# STM32_AUX.net
KiCad netlist of a schematic drawn in Altium Designer
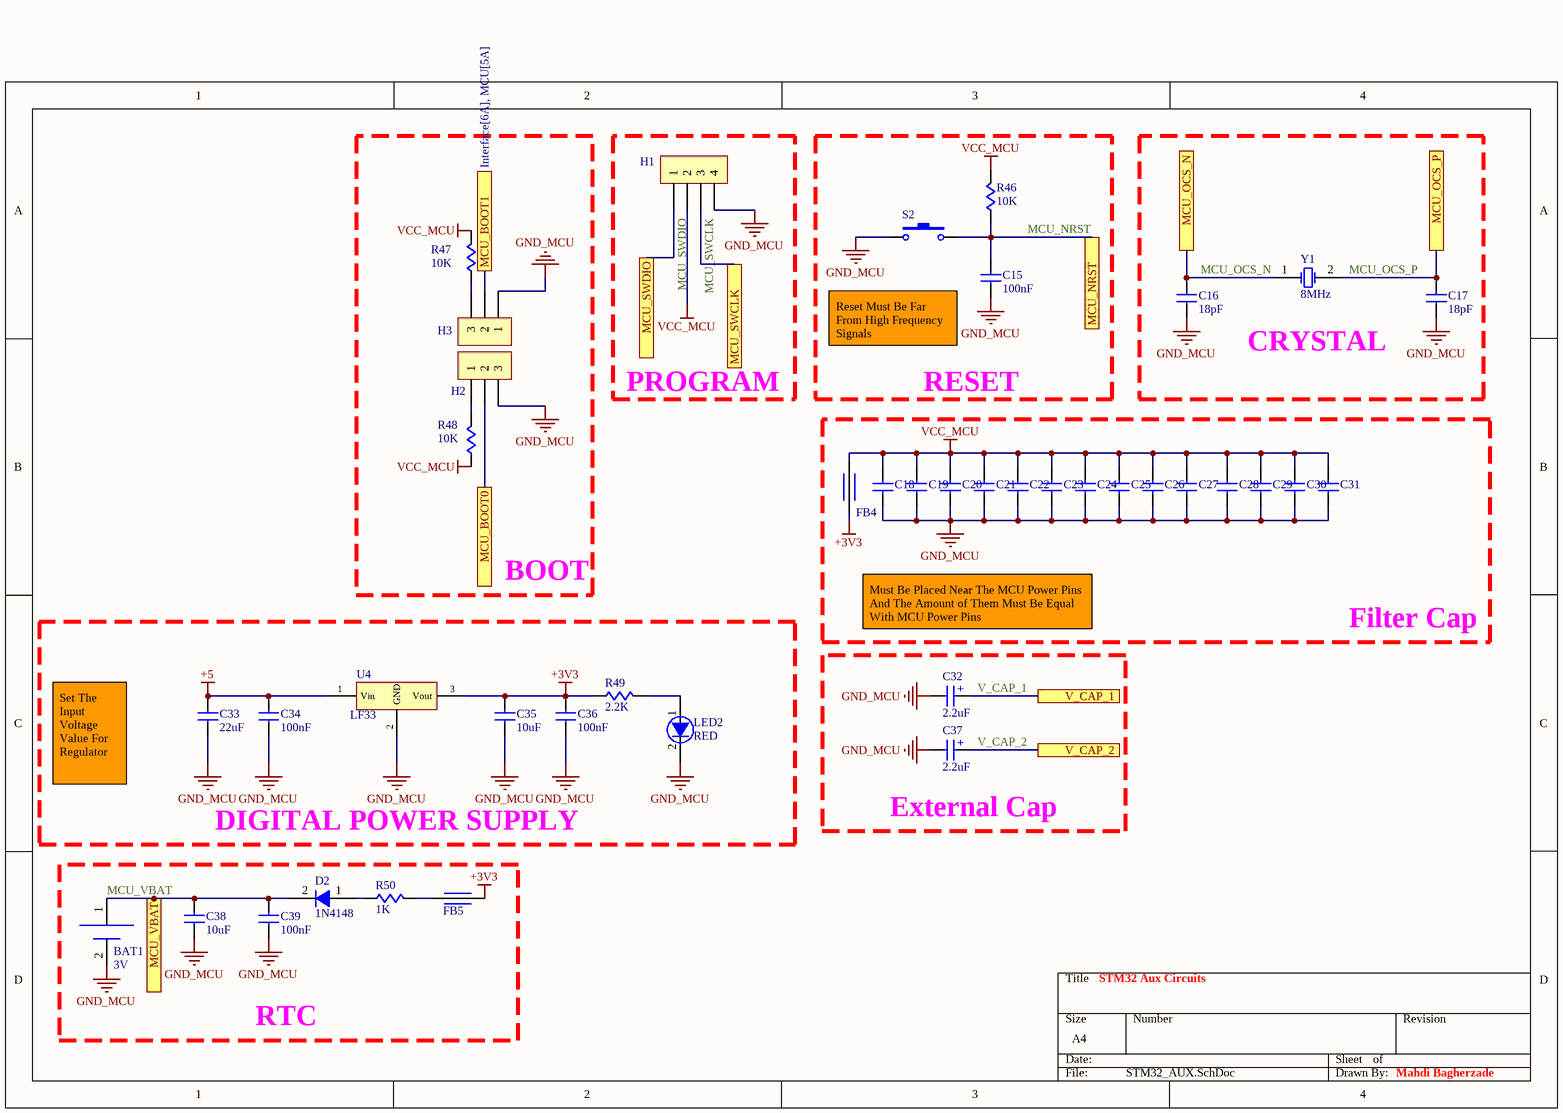
[diagram p0: STM32_AUX.SchDoc]

(export (version "E")
  (design (tool "Eeschema 10.0.6"))
  (components
    (comp (ref "BAT1")
      (value "Bat Holder 2016-SMD")
      (footprint "BAT-HOLDER-SMD-1220")
      (description "BATTERY")
      (fields (field (name "VOLTAGE") "3V") (field (name "PUBLISHER") "Mahdi Bagherzadeh"))
      (libsource (lib "Mahdi-Bagherzadeh") (part "BATTERY HOLDER"))
    )
    (comp (ref "C15")
      (value "100nF")
      (footprint "C-0805")
      (description "CAPACITOR")
      (fields
        (field (name "VOLTAGE") "50V")
        (field (name "TOLERANCE") "X7R")
        (field (name "PUBLISHER") "Mahdi Bagherzadeh")
      )
      (libsource (lib "Mahdi-Bagherzadeh") (part "CAP-CER"))
    )
    (comp (ref "C16")
      (value "18pF")
      (footprint "C-0805")
      (description "CAPACITOR")
      (fields
        (field (name "VOLTAGE") "50V")
        (field (name "TOLERANCE") "X7R")
        (field (name "PUBLISHER") "Mahdi Bagherzadeh")
      )
      (libsource (lib "Mahdi-Bagherzadeh") (part "CAP-CER"))
    )
    (comp (ref "C17")
      (value "18pF")
      (footprint "C-0805")
      (description "CAPACITOR")
      (fields
        (field (name "VOLTAGE") "50V")
        (field (name "TOLERANCE") "X7R")
        (field (name "PUBLISHER") "Mahdi Bagherzadeh")
      )
      (libsource (lib "Mahdi-Bagherzadeh") (part "CAP-CER"))
    )
    (comp (ref "C18")
      (value "CAP Cer 100nF-50V-X7R-SMD")
      (footprint "C-0805")
      (description "CAPACITOR")
      (fields
        (field (name "VOLTAGE") "50V")
        (field (name "TOLERANCE") "X7R")
        (field (name "PUBLISHER") "Mahdi Bagherzadeh")
      )
      (libsource (lib "Mahdi-Bagherzadeh") (part "CAP-CER"))
    )
    (comp (ref "C19")
      (value "CAP Cer 100nF-50V-X7R-SMD")
      (footprint "C-0805")
      (description "CAPACITOR")
      (fields
        (field (name "VOLTAGE") "50V")
        (field (name "TOLERANCE") "X7R")
        (field (name "PUBLISHER") "Mahdi Bagherzadeh")
      )
      (libsource (lib "Mahdi-Bagherzadeh") (part "CAP-CER"))
    )
    (comp (ref "C20")
      (value "CAP Cer 100nF-50V-X7R-SMD")
      (footprint "C-0805")
      (description "CAPACITOR")
      (fields
        (field (name "VOLTAGE") "50V")
        (field (name "TOLERANCE") "X7R")
        (field (name "PUBLISHER") "Mahdi Bagherzadeh")
      )
      (libsource (lib "Mahdi-Bagherzadeh") (part "CAP-CER"))
    )
    (comp (ref "C21")
      (value "CAP Cer 100nF-50V-X7R-SMD")
      (footprint "C-0805")
      (description "CAPACITOR")
      (fields
        (field (name "VOLTAGE") "50V")
        (field (name "TOLERANCE") "X7R")
        (field (name "PUBLISHER") "Mahdi Bagherzadeh")
      )
      (libsource (lib "Mahdi-Bagherzadeh") (part "CAP-CER"))
    )
    (comp (ref "C22")
      (value "CAP Cer 100nF-50V-X7R-SMD")
      (footprint "C-0805")
      (description "CAPACITOR")
      (fields
        (field (name "VOLTAGE") "50V")
        (field (name "TOLERANCE") "X7R")
        (field (name "PUBLISHER") "Mahdi Bagherzadeh")
      )
      (libsource (lib "Mahdi-Bagherzadeh") (part "CAP-CER"))
    )
    (comp (ref "C23")
      (value "CAP Cer 100nF-50V-X7R-SMD")
      (footprint "C-0805")
      (description "CAPACITOR")
      (fields
        (field (name "VOLTAGE") "50V")
        (field (name "TOLERANCE") "X7R")
        (field (name "PUBLISHER") "Mahdi Bagherzadeh")
      )
      (libsource (lib "Mahdi-Bagherzadeh") (part "CAP-CER"))
    )
    (comp (ref "C24")
      (value "CAP Cer 100nF-50V-X7R-SMD")
      (footprint "C-0805")
      (description "CAPACITOR")
      (fields
        (field (name "VOLTAGE") "50V")
        (field (name "TOLERANCE") "X7R")
        (field (name "PUBLISHER") "Mahdi Bagherzadeh")
      )
      (libsource (lib "Mahdi-Bagherzadeh") (part "CAP-CER"))
    )
    (comp (ref "C25")
      (value "CAP Cer 100nF-50V-X7R-SMD")
      (footprint "C-0805")
      (description "CAPACITOR")
      (fields
        (field (name "VOLTAGE") "50V")
        (field (name "TOLERANCE") "X7R")
        (field (name "PUBLISHER") "Mahdi Bagherzadeh")
      )
      (libsource (lib "Mahdi-Bagherzadeh") (part "CAP-CER"))
    )
    (comp (ref "C26")
      (value "CAP Cer 100nF-50V-X7R-SMD")
      (footprint "C-0805")
      (description "CAPACITOR")
      (fields
        (field (name "VOLTAGE") "50V")
        (field (name "TOLERANCE") "X7R")
        (field (name "PUBLISHER") "Mahdi Bagherzadeh")
      )
      (libsource (lib "Mahdi-Bagherzadeh") (part "CAP-CER"))
    )
    (comp (ref "C27")
      (value "CAP Cer 100nF-50V-X7R-SMD")
      (footprint "C-0805")
      (description "CAPACITOR")
      (fields
        (field (name "VOLTAGE") "50V")
        (field (name "TOLERANCE") "X7R")
        (field (name "PUBLISHER") "Mahdi Bagherzadeh")
      )
      (libsource (lib "Mahdi-Bagherzadeh") (part "CAP-CER"))
    )
    (comp (ref "C28")
      (value "CAP Cer 100nF-50V-X7R-SMD")
      (footprint "C-0805")
      (description "CAPACITOR")
      (fields
        (field (name "VOLTAGE") "50V")
        (field (name "TOLERANCE") "X7R")
        (field (name "PUBLISHER") "Mahdi Bagherzadeh")
      )
      (libsource (lib "Mahdi-Bagherzadeh") (part "CAP-CER"))
    )
    (comp (ref "C29")
      (value "CAP Cer 100nF-50V-X7R-SMD")
      (footprint "C-0805")
      (description "CAPACITOR")
      (fields
        (field (name "VOLTAGE") "50V")
        (field (name "TOLERANCE") "X7R")
        (field (name "PUBLISHER") "Mahdi Bagherzadeh")
      )
      (libsource (lib "Mahdi-Bagherzadeh") (part "CAP-CER"))
    )
    (comp (ref "C30")
      (value "CAP Cer 100nF-50V-X7R-SMD")
      (footprint "C-0805")
      (description "CAPACITOR")
      (fields
        (field (name "VOLTAGE") "50V")
        (field (name "TOLERANCE") "X7R")
        (field (name "PUBLISHER") "Mahdi Bagherzadeh")
      )
      (libsource (lib "Mahdi-Bagherzadeh") (part "CAP-CER"))
    )
    (comp (ref "C31")
      (value "CAP Cer 100nF-50V-X7R-SMD")
      (footprint "C-0805")
      (description "CAPACITOR")
      (fields
        (field (name "VOLTAGE") "50V")
        (field (name "TOLERANCE") "X7R")
        (field (name "PUBLISHER") "Mahdi Bagherzadeh")
      )
      (libsource (lib "Mahdi-Bagherzadeh") (part "CAP-CER"))
    )
    (comp (ref "C32")
      (value "2.2uF")
      (footprint "TAN-A")
      (description "CAPACITOR")
      (fields
        (field (name "VOLTAGE") "10V")
        (field (name "Comment") "CAP Tantal 2.2uF-10V-A-SMD")
        (field (name "PUBLISHER") "Mahdi Bagherzadeh")
      )
      (libsource (lib "Mahdi-Bagherzadeh") (part "CAP-TAN"))
    )
    (comp (ref "C33")
      (value "22uF")
      (footprint "C-0805")
      (description "CAPACITOR")
      (fields
        (field (name "VOLTAGE") "50V")
        (field (name "TOLERANCE") "X7R")
        (field (name "PUBLISHER") "Mahdi Bagherzadeh")
      )
      (libsource (lib "Mahdi-Bagherzadeh") (part "CAP-CER"))
    )
    (comp (ref "C34")
      (value "100nF")
      (footprint "C-0805")
      (description "CAPACITOR")
      (fields
        (field (name "VOLTAGE") "50V")
        (field (name "TOLERANCE") "X7R")
        (field (name "PUBLISHER") "Mahdi Bagherzadeh")
      )
      (libsource (lib "Mahdi-Bagherzadeh") (part "CAP-CER"))
    )
    (comp (ref "C35")
      (value "10uF")
      (footprint "C-0805")
      (description "CAPACITOR")
      (fields
        (field (name "VOLTAGE") "50V")
        (field (name "TOLERANCE") "X7R")
        (field (name "PUBLISHER") "Mahdi Bagherzadeh")
      )
      (libsource (lib "Mahdi-Bagherzadeh") (part "CAP-CER"))
    )
    (comp (ref "C36")
      (value "100nF")
      (footprint "C-0805")
      (description "CAPACITOR")
      (fields
        (field (name "VOLTAGE") "50V")
        (field (name "TOLERANCE") "X7R")
        (field (name "PUBLISHER") "Mahdi Bagherzadeh")
      )
      (libsource (lib "Mahdi-Bagherzadeh") (part "CAP-CER"))
    )
    (comp (ref "C37")
      (value "2.2uF")
      (footprint "TAN-A")
      (description "CAPACITOR")
      (fields
        (field (name "VOLTAGE") "10V")
        (field (name "Comment") "CAP Tantal 2.2uF-10V-A-SMD")
        (field (name "PUBLISHER") "Mahdi Bagherzadeh")
      )
      (libsource (lib "Mahdi-Bagherzadeh") (part "CAP-TAN"))
    )
    (comp (ref "C38")
      (value "10uF")
      (footprint "C-0805")
      (description "CAPACITOR")
      (fields
        (field (name "VOLTAGE") "50V")
        (field (name "TOLERANCE") "X7R")
        (field (name "PUBLISHER") "Mahdi Bagherzadeh")
      )
      (libsource (lib "Mahdi-Bagherzadeh") (part "CAP-CER"))
    )
    (comp (ref "C39")
      (value "100nF")
      (footprint "C-0805")
      (description "CAPACITOR")
      (fields
        (field (name "VOLTAGE") "50V")
        (field (name "TOLERANCE") "X7R")
        (field (name "PUBLISHER") "Mahdi Bagherzadeh")
      )
      (libsource (lib "Mahdi-Bagherzadeh") (part "CAP-CER"))
    )
    (comp (ref "D2")
      (value "Diode 1N4148-SMD")
      (footprint "SOD80")
      (description "DIODE")
      (fields (field (name "CODE") "1N4148") (field (name "PUBLISHER") "Mahdi Bagherzadeh"))
      (libsource (lib "Mahdi-Bagherzadeh") (part "DIODE"))
    )
    (comp (ref "FB4")
      (value "FERRITE BEAD")
      (footprint "FB-0805")
      (description "INDUCATOR")
      (fields (field (name "PUBLISHER") "Mahdi Bagherzadeh"))
      (libsource (lib "Mahdi-Bagherzadeh") (part "FERRITE BEAD"))
    )
    (comp (ref "FB5")
      (value "Ferrite Bead SMD")
      (footprint "FB-0805")
      (description "INDUCATOR")
      (fields (field (name "PUBLISHER") "Mahdi Bagherzadeh"))
      (libsource (lib "Mahdi-Bagherzadeh") (part "FERRITE BEAD"))
    )
    (comp (ref "H1")
      (value "Header 4x1 Pin -Straight-Male-2.54mm")
      (footprint "H-4pin-M-S")
      (description "HEADER")
      (fields (field (name "PUBLISHER") "Mahdi Bagherzadeh"))
      (libsource (lib "Mahdi-Bagherzadeh") (part "HEADER-4pin"))
    )
    (comp (ref "H2")
      (value "Header 3x1 Pin -Straight-Male-2.54mm")
      (footprint "H-3pin-M-S")
      (description "HEADER")
      (fields (field (name "PUBLISHER") "Mahdi Bagherzadeh"))
      (libsource (lib "Mahdi-Bagherzadeh") (part "HEADER-3pin"))
    )
    (comp (ref "H3")
      (value "Header 3x1 Pin -Straight-Male-2.54mm")
      (footprint "H-3pin-M-S")
      (description "HEADER")
      (fields (field (name "PUBLISHER") "Mahdi Bagherzadeh"))
      (libsource (lib "") (part "HEADER-3pin_1"))
    )
    (comp (ref "LED2")
      (value "LED RED-1206-SMD")
      (footprint "LED-1206-R")
      (description "LED")
      (fields (field (name "COLOR") "RED") (field (name "PUBLISHER") "Mahdi Bagherzadeh"))
      (libsource (lib "Mahdi-Bagherzadeh") (part "LED"))
    )
    (comp (ref "R46")
      (value "10K")
      (footprint "R-0805")
      (description "RESISTOR")
      (fields
        (field (name "TOLERANCE") "5%")
        (field (name "POWER") "1/8W")
        (field (name "PUBLISHER") "Mahdi Bagherzadeh")
      )
      (libsource (lib "Mahdi-Bagherzadeh") (part "RES"))
    )
    (comp (ref "R47")
      (value "10K")
      (footprint "R-0805")
      (description "RESISTOR")
      (fields
        (field (name "TOLERANCE") "5%")
        (field (name "POWER") "1/8W")
        (field (name "PUBLISHER") "Mahdi Bagherzadeh")
      )
      (libsource (lib "Mahdi-Bagherzadeh") (part "RES"))
    )
    (comp (ref "R48")
      (value "10K")
      (footprint "R-0805")
      (description "RESISTOR")
      (fields
        (field (name "TOLERANCE") "5%")
        (field (name "POWER") "1/8W")
        (field (name "PUBLISHER") "Mahdi Bagherzadeh")
      )
      (libsource (lib "Mahdi-Bagherzadeh") (part "RES"))
    )
    (comp (ref "R49")
      (value "2.2K")
      (footprint "R-0805")
      (description "RESISTOR")
      (fields
        (field (name "TOLERANCE") "5%")
        (field (name "POWER") "1/8W")
        (field (name "PUBLISHER") "Mahdi Bagherzadeh")
      )
      (libsource (lib "Mahdi-Bagherzadeh") (part "RES"))
    )
    (comp (ref "R50")
      (value "1K")
      (footprint "R-0805")
      (description "RESISTOR")
      (fields
        (field (name "TOLERANCE") "5%")
        (field (name "POWER") "1/8W")
        (field (name "PUBLISHER") "Mahdi Bagherzadeh")
      )
      (libsource (lib "Mahdi-Bagherzadeh") (part "RES"))
    )
    (comp (ref "S2")
      (value "Push Button 3x6mm-2Pin-SMD")
      (footprint "SW-SMD-2pin-3x6")
      (description "SWITCH")
      (fields (field (name "PUBLISHER") "Mahdi Bagherzadeh"))
      (libsource (lib "Mahdi-Bagherzadeh") (part "PUSH BUTTON"))
    )
    (comp (ref "U4")
      (value "Reg LF33-3.3V-SMD")
      (footprint "TO252-3pin")
      (description "REGULATOR")
      (fields
        (field (name "VOLTAGE") "3.3V")
        (field (name "CODE") "LF33")
        (field (name "PUBLISHER") "Mahdi Bagherzadeh")
      )
      (libsource (lib "Mahdi-Bagherzadeh") (part "LF33"))
    )
    (comp (ref "Y1")
      (value "8MHz")
      (footprint "CRYSTAL-SMD")
      (description "CRYSTAL")
      (fields (field (name "Comment") "Crystal 8MHz-SMD") (field (name "PUBLISHER") "Mahdi Bagherzadeh"))
      (libsource (lib "Mahdi-Bagherzadeh") (part "CRYSTAL"))
    )
  )
  (nets
    (net (code "1") (name "+3V3") (class "Default")
      (node (ref "C35") (pin "2") (pinfunction "2_2") (pintype "passive"))
      (node (ref "C36") (pin "2") (pinfunction "2_2") (pintype "passive"))
      (node (ref "FB4") (pin "1") (pinfunction "1_1") (pintype "passive"))
      (node (ref "FB5") (pin "1") (pinfunction "1_1") (pintype "passive"))
      (node (ref "R49") (pin "1") (pinfunction "1_1") (pintype "passive"))
      (node (ref "U4") (pin "3") (pinfunction "Vout_3") (pintype "power_in"))
    )
    (net (code "2") (name "+5") (class "Default")
      (node (ref "C33") (pin "2") (pinfunction "2_2") (pintype "passive"))
      (node (ref "C34") (pin "2") (pinfunction "2_2") (pintype "passive"))
      (node (ref "U4") (pin "1") (pinfunction "Vin_1") (pintype "power_in"))
    )
    (net (code "3") (name "/MCU_BOOT0") (class "Default")
      (node (ref "H2") (pin "2") (pinfunction "2_2") (pintype "passive"))
    )
    (net (code "4") (name "/MCU_BOOT1") (class "Default")
      (node (ref "H3") (pin "2") (pinfunction "2_2") (pintype "passive"))
    )
    (net (code "5") (name "/MCU_NRST") (class "Default")
      (node (ref "C15") (pin "2") (pinfunction "2_2") (pintype "passive"))
      (node (ref "R46") (pin "1") (pinfunction "1_1") (pintype "passive"))
      (node (ref "S2") (pin "2") (pinfunction "2_2") (pintype "passive"))
    )
    (net (code "6") (name "/MCU_OCS_N") (class "Default")
      (node (ref "C16") (pin "2") (pinfunction "2_2") (pintype "passive"))
      (node (ref "Y1") (pin "1") (pinfunction "OSC1_1") (pintype "passive"))
    )
    (net (code "7") (name "/MCU_OCS_P") (class "Default")
      (node (ref "C17") (pin "2") (pinfunction "2_2") (pintype "passive"))
      (node (ref "Y1") (pin "2") (pinfunction "OSC2_2") (pintype "passive"))
    )
    (net (code "8") (name "/MCU_SWCLK") (class "Default")
      (node (ref "H1") (pin "3") (pinfunction "3_3") (pintype "passive"))
    )
    (net (code "9") (name "/MCU_SWDIO") (class "Default")
      (node (ref "H1") (pin "1") (pinfunction "1_1") (pintype "passive"))
    )
    (net (code "10") (name "/MCU_VBAT") (class "Default")
      (node (ref "BAT1") (pin "1") (pinfunction "+_1") (pintype "passive"))
      (node (ref "C38") (pin "2") (pinfunction "2_2") (pintype "passive"))
      (node (ref "C39") (pin "2") (pinfunction "2_2") (pintype "passive"))
      (node (ref "D2") (pin "2") (pinfunction "C_2") (pintype "passive"))
    )
    (net (code "11") (name "/V_CAP_1") (class "Default")
      (node (ref "C32") (pin "1") (pinfunction "1_1") (pintype "passive"))
    )
    (net (code "12") (name "/V_CAP_2") (class "Default")
      (node (ref "C37") (pin "1") (pinfunction "1_1") (pintype "passive"))
    )
    (net (code "13") (name "GND_MCU") (class "Default")
      (node (ref "BAT1") (pin "2") (pinfunction "-_2") (pintype "passive"))
      (node (ref "C15") (pin "1") (pinfunction "1_1") (pintype "passive"))
      (node (ref "C16") (pin "1") (pinfunction "1_1") (pintype "passive"))
      (node (ref "C17") (pin "1") (pinfunction "1_1") (pintype "passive"))
      (node (ref "C18") (pin "2") (pinfunction "2_2") (pintype "passive"))
      (node (ref "C19") (pin "2") (pinfunction "2_2") (pintype "passive"))
      (node (ref "C20") (pin "2") (pinfunction "2_2") (pintype "passive"))
      (node (ref "C21") (pin "2") (pinfunction "2_2") (pintype "passive"))
      (node (ref "C22") (pin "2") (pinfunction "2_2") (pintype "passive"))
      (node (ref "C23") (pin "2") (pinfunction "2_2") (pintype "passive"))
      (node (ref "C24") (pin "2") (pinfunction "2_2") (pintype "passive"))
      (node (ref "C25") (pin "2") (pinfunction "2_2") (pintype "passive"))
      (node (ref "C26") (pin "2") (pinfunction "2_2") (pintype "passive"))
      (node (ref "C27") (pin "2") (pinfunction "2_2") (pintype "passive"))
      (node (ref "C28") (pin "2") (pinfunction "2_2") (pintype "passive"))
      (node (ref "C29") (pin "2") (pinfunction "2_2") (pintype "passive"))
      (node (ref "C30") (pin "2") (pinfunction "2_2") (pintype "passive"))
      (node (ref "C31") (pin "2") (pinfunction "2_2") (pintype "passive"))
      (node (ref "C32") (pin "2") (pinfunction "2_2") (pintype "passive"))
      (node (ref "C33") (pin "1") (pinfunction "1_1") (pintype "passive"))
      (node (ref "C34") (pin "1") (pinfunction "1_1") (pintype "passive"))
      (node (ref "C35") (pin "1") (pinfunction "1_1") (pintype "passive"))
      (node (ref "C36") (pin "1") (pinfunction "1_1") (pintype "passive"))
      (node (ref "C37") (pin "2") (pinfunction "2_2") (pintype "passive"))
      (node (ref "C38") (pin "1") (pinfunction "1_1") (pintype "passive"))
      (node (ref "C39") (pin "1") (pinfunction "1_1") (pintype "passive"))
      (node (ref "H1") (pin "4") (pinfunction "4_4") (pintype "passive"))
      (node (ref "H2") (pin "3") (pinfunction "3_3") (pintype "passive"))
      (node (ref "H3") (pin "1") (pinfunction "1_1") (pintype "passive"))
      (node (ref "LED2") (pin "2") (pinfunction "C_2") (pintype "passive"))
      (node (ref "S2") (pin "1") (pinfunction "1_1") (pintype "passive"))
      (node (ref "U4") (pin "2") (pinfunction "GND_2") (pintype "power_in"))
    )
    (net (code "14") (name "Net-(D2-A)") (class "Default")
      (node (ref "D2") (pin "1") (pinfunction "A_1") (pintype "passive"))
      (node (ref "R50") (pin "1") (pinfunction "1_1") (pintype "passive"))
    )
    (net (code "15") (name "Net-(FB5-Pad2)") (class "Default")
      (node (ref "FB5") (pin "2") (pinfunction "2_2") (pintype "passive"))
      (node (ref "R50") (pin "2") (pinfunction "2_2") (pintype "passive"))
    )
    (net (code "16") (name "Net-(H2-Pad1)") (class "Default")
      (node (ref "H2") (pin "1") (pinfunction "1_1") (pintype "passive"))
      (node (ref "R48") (pin "2") (pinfunction "2_2") (pintype "passive"))
    )
    (net (code "17") (name "Net-(H3-Pad3)") (class "Default")
      (node (ref "H3") (pin "3") (pinfunction "3_3") (pintype "passive"))
      (node (ref "R47") (pin "2") (pinfunction "2_2") (pintype "passive"))
    )
    (net (code "18") (name "Net-(LED2-A)") (class "Default")
      (node (ref "LED2") (pin "1") (pinfunction "A_1") (pintype "passive"))
      (node (ref "R49") (pin "2") (pinfunction "2_2") (pintype "passive"))
    )
    (net (code "19") (name "VCC_MCU") (class "Default")
      (node (ref "C18") (pin "1") (pinfunction "1_1") (pintype "passive"))
      (node (ref "C19") (pin "1") (pinfunction "1_1") (pintype "passive"))
      (node (ref "C20") (pin "1") (pinfunction "1_1") (pintype "passive"))
      (node (ref "C21") (pin "1") (pinfunction "1_1") (pintype "passive"))
      (node (ref "C22") (pin "1") (pinfunction "1_1") (pintype "passive"))
      (node (ref "C23") (pin "1") (pinfunction "1_1") (pintype "passive"))
      (node (ref "C24") (pin "1") (pinfunction "1_1") (pintype "passive"))
      (node (ref "C25") (pin "1") (pinfunction "1_1") (pintype "passive"))
      (node (ref "C26") (pin "1") (pinfunction "1_1") (pintype "passive"))
      (node (ref "C27") (pin "1") (pinfunction "1_1") (pintype "passive"))
      (node (ref "C28") (pin "1") (pinfunction "1_1") (pintype "passive"))
      (node (ref "C29") (pin "1") (pinfunction "1_1") (pintype "passive"))
      (node (ref "C30") (pin "1") (pinfunction "1_1") (pintype "passive"))
      (node (ref "C31") (pin "1") (pinfunction "1_1") (pintype "passive"))
      (node (ref "FB4") (pin "2") (pinfunction "2_2") (pintype "passive"))
      (node (ref "H1") (pin "2") (pinfunction "2_2") (pintype "passive"))
      (node (ref "R46") (pin "2") (pinfunction "2_2") (pintype "passive"))
      (node (ref "R47") (pin "1") (pinfunction "1_1") (pintype "passive"))
      (node (ref "R48") (pin "1") (pinfunction "1_1") (pintype "passive"))
    )
  )
)
